# Jukebox.net
KiCad netlist of a schematic drawn in EAGLE
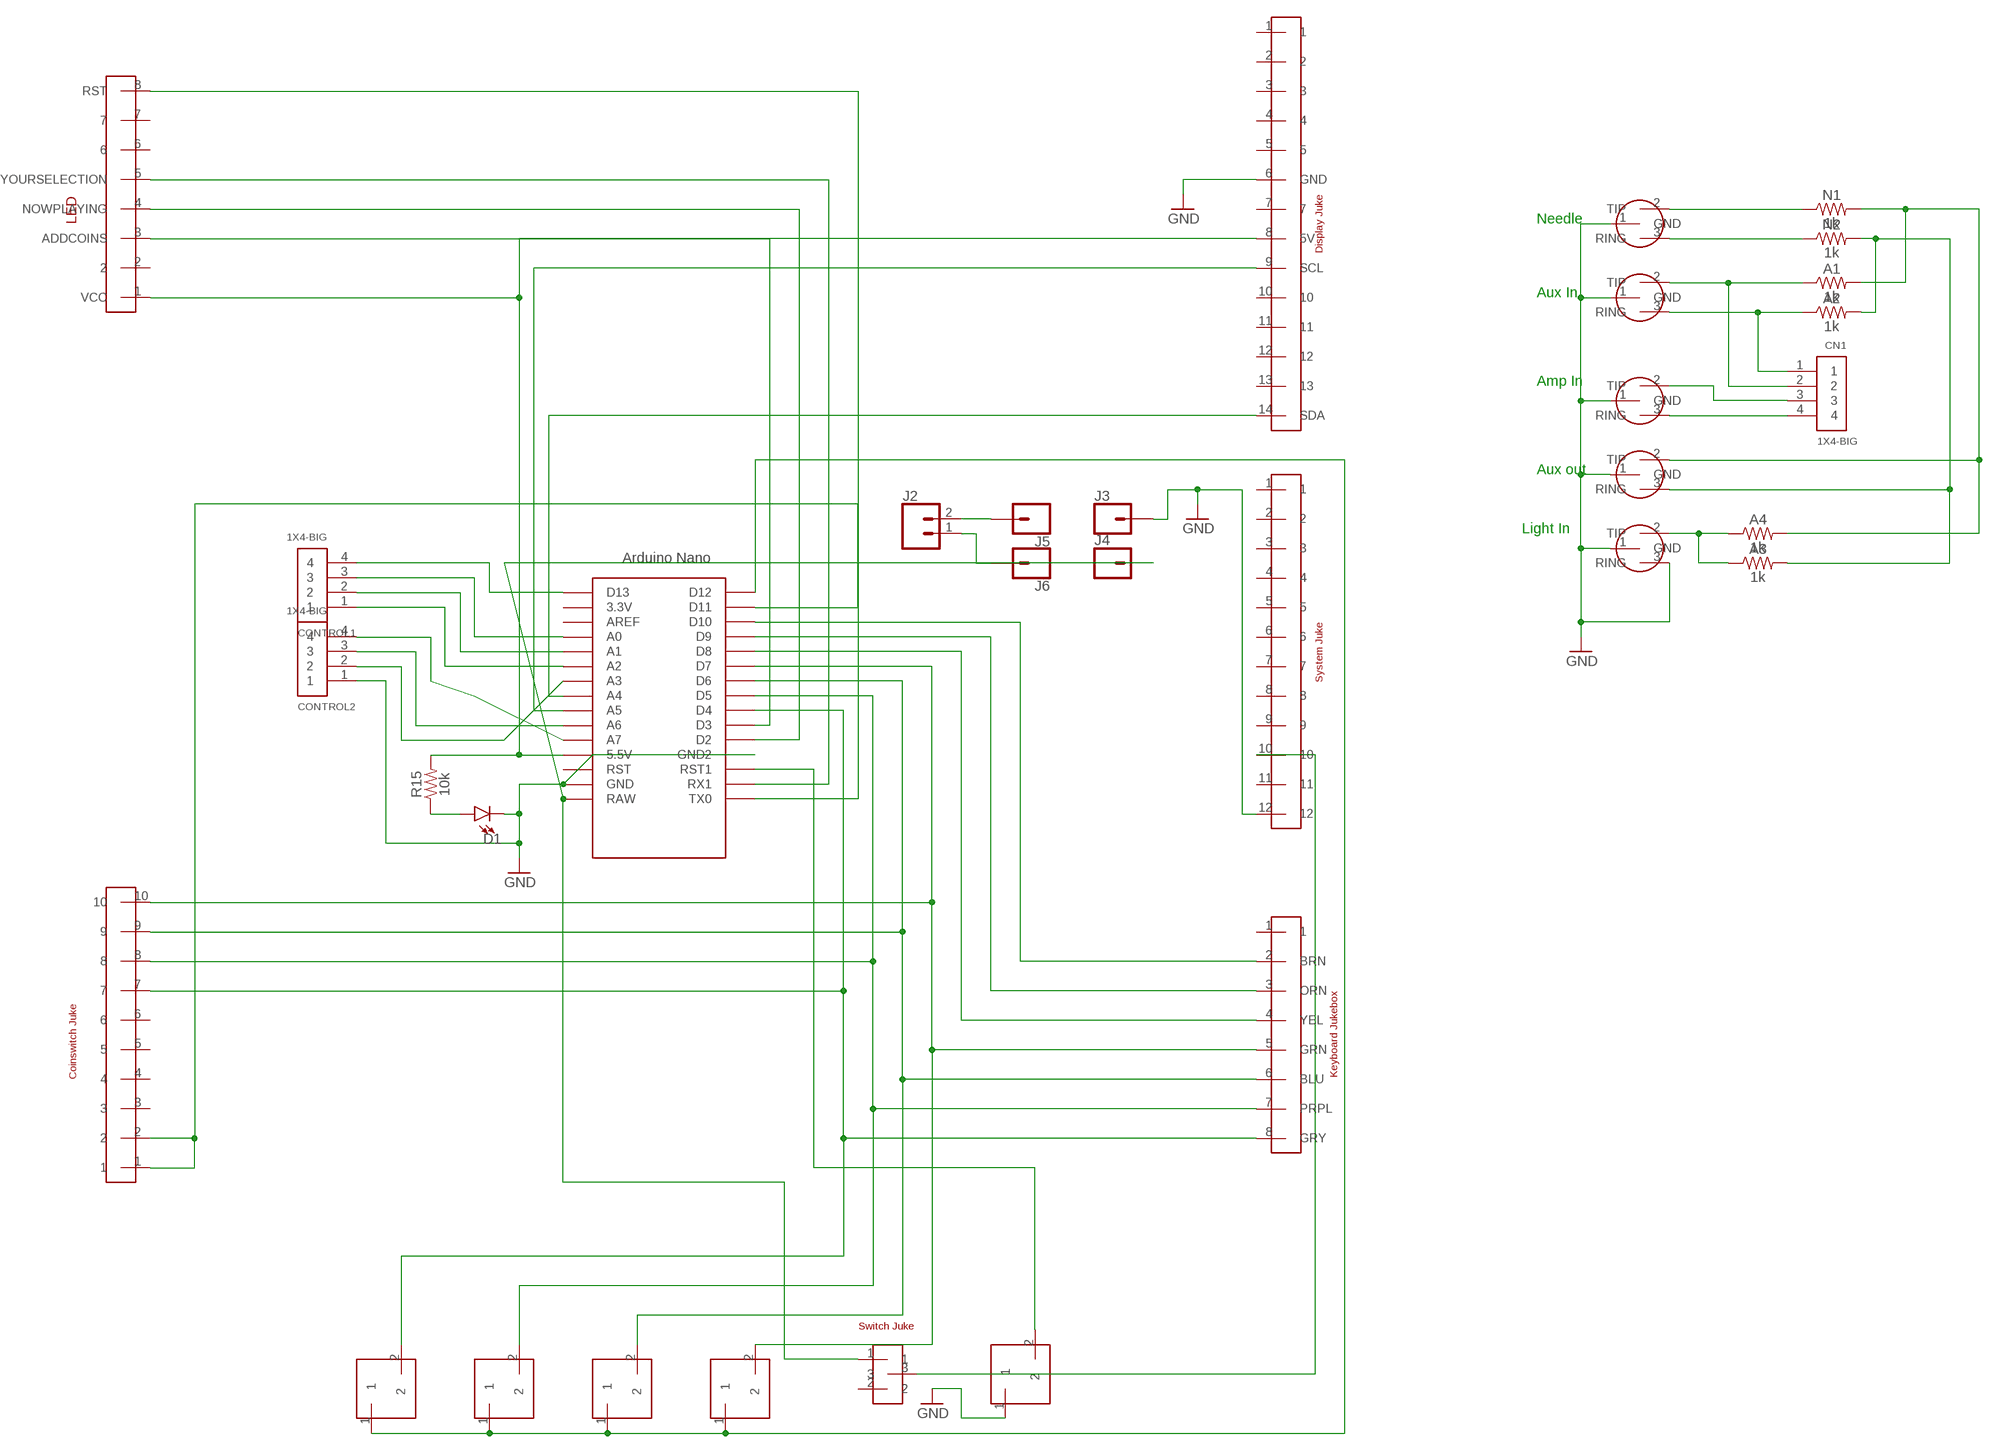
[diagram p0: schematic, sheet 1]

(export (version "E")
  (design (tool "Eeschema 10.0.6"))
  (components
    (comp (ref "A1")
      (value "1k")
      (footprint "eagle-import:AXIAL-0.3")
      (libsource (lib "eagle-import") (part "10KOHM-HORIZ-1/4W-1%"))
    )
    (comp (ref "A2")
      (value "1k")
      (footprint "eagle-import:AXIAL-0.3")
      (libsource (lib "eagle-import") (part "10KOHM-HORIZ-1/4W-1%"))
    )
    (comp (ref "A3")
      (value "1k")
      (footprint "eagle-import:AXIAL-0.3")
      (libsource (lib "eagle-import") (part "10KOHM-HORIZ-1/4W-1%"))
    )
    (comp (ref "A4")
      (value "1k")
      (footprint "eagle-import:AXIAL-0.3")
      (libsource (lib "eagle-import") (part "10KOHM-HORIZ-1/4W-1%"))
    )
    (comp (ref "AUXIN")
      (value "JUKEHEADPHONE")
      (footprint "eagle-import:JUKEHEADPHONE")
      (libsource (lib "eagle-import") (part "JUKEHEADPHONE"))
    )
    (comp (ref "AUXOUT")
      (value "JUKEHEADPHONE")
      (footprint "eagle-import:JUKEHEADPHONE")
      (libsource (lib "eagle-import") (part "JUKEHEADPHONE"))
    )
    (comp (ref "CN1")
      (value "1X4-BIG")
      (footprint "eagle-import:1X04-BIG")
      (libsource (lib "eagle-import") (part "1X4-BIG"))
    )
    (comp (ref "CONTROL1")
      (value "1X4-BIG")
      (footprint "eagle-import:1X04-BIG")
      (libsource (lib "eagle-import") (part "1X4-BIG"))
    )
    (comp (ref "CONTROL2")
      (value "1X4-BIG")
      (footprint "eagle-import:1X04-BIG")
      (libsource (lib "eagle-import") (part "1X4-BIG"))
    )
    (comp (ref "D1")
      (value "LED5MM")
      (footprint "eagle-import:LED_5MM")
      (libsource (lib "eagle-import") (part "LED5MM"))
    )
    (comp (ref "FROMNEEDLE")
      (value "JUKEHEADPHONE")
      (footprint "eagle-import:JUKEHEADPHONE")
      (libsource (lib "eagle-import") (part "JUKEHEADPHONE"))
    )
    (comp (ref "J2")
      (value "CONN_02")
      (footprint "eagle-import:1X02")
      (libsource (lib "eagle-import") (part "CONN_02"))
    )
    (comp (ref "J3")
      (value "CONN_01")
      (footprint "eagle-import:1X01")
      (libsource (lib "eagle-import") (part "CONN_01"))
    )
    (comp (ref "J4")
      (value "CONN_01")
      (footprint "eagle-import:1X01")
      (libsource (lib "eagle-import") (part "CONN_01"))
    )
    (comp (ref "J5")
      (value "CONN_01")
      (footprint "eagle-import:1X01")
      (libsource (lib "eagle-import") (part "CONN_01"))
    )
    (comp (ref "J6")
      (value "CONN_01")
      (footprint "eagle-import:1X01")
      (libsource (lib "eagle-import") (part "CONN_01"))
    )
    (comp (ref "N1")
      (value "1k")
      (footprint "eagle-import:AXIAL-0.3")
      (libsource (lib "eagle-import") (part "10KOHM-HORIZ-1/4W-1%"))
    )
    (comp (ref "N2")
      (value "1k")
      (footprint "eagle-import:AXIAL-0.3")
      (libsource (lib "eagle-import") (part "10KOHM-HORIZ-1/4W-1%"))
    )
    (comp (ref "R15")
      (value "10k")
      (footprint "eagle-import:AXIAL-0.3")
      (libsource (lib "eagle-import") (part "10KOHM-HORIZ-1/4W-1%"))
    )
    (comp (ref "TOAMP")
      (value "JUKEHEADPHONE")
      (footprint "eagle-import:JUKEHEADPHONE")
      (libsource (lib "eagle-import") (part "JUKEHEADPHONE"))
    )
    (comp (ref "TOLIGHT")
      (value "JUKEHEADPHONE")
      (footprint "eagle-import:JUKEHEADPHONE")
      (libsource (lib "eagle-import") (part "JUKEHEADPHONE"))
    )
    (comp (ref "U$1")
      (value "NANO")
      (footprint "eagle-import:NANO")
      (libsource (lib "eagle-import") (part "NANO"))
    )
    (comp (ref "U$5")
      (value "10PINJUKE")
      (footprint "eagle-import:10PINJUKE")
      (libsource (lib "eagle-import") (part "10PINJUKE"))
    )
    (comp (ref "U$6")
      (value "8PINJUKE")
      (footprint "eagle-import:8PINJUKE")
      (libsource (lib "eagle-import") (part "8PINJUKE"))
    )
    (comp (ref "U$7")
      (value "14PINJUKE")
      (footprint "eagle-import:14PINJUKE")
      (libsource (lib "eagle-import") (part "14PINJUKE"))
    )
    (comp (ref "U$8")
      (value "12PINJUKE")
      (footprint "eagle-import:12PINJUKE")
      (libsource (lib "eagle-import") (part "12PINJUKE"))
    )
    (comp (ref "U$9")
      (value "JUKEBUTTON")
      (footprint "eagle-import:JUKEBUTTON")
      (libsource (lib "eagle-import") (part "JUKEBUTTON"))
    )
    (comp (ref "U$10")
      (value "JUKEBUTTON")
      (footprint "eagle-import:JUKEBUTTON")
      (libsource (lib "eagle-import") (part "JUKEBUTTON"))
    )
    (comp (ref "U$11")
      (value "JUKEBUTTON")
      (footprint "eagle-import:JUKEBUTTON")
      (libsource (lib "eagle-import") (part "JUKEBUTTON"))
    )
    (comp (ref "U$12")
      (value "JUKEBUTTON")
      (footprint "eagle-import:JUKEBUTTON")
      (libsource (lib "eagle-import") (part "JUKEBUTTON"))
    )
    (comp (ref "U$13")
      (value "JUKEBUTTON")
      (footprint "eagle-import:JUKEBUTTON")
      (libsource (lib "eagle-import") (part "JUKEBUTTON"))
    )
    (comp (ref "U$14")
      (value "JUKESWITCH")
      (footprint "eagle-import:JUKESWITCH")
      (libsource (lib "eagle-import") (part "JUKESWITCH"))
    )
    (comp (ref "U$17")
      (value "8PINJUKE2")
      (footprint "eagle-import:8PINJUKE")
      (libsource (lib "eagle-import") (part "8PINJUKE2"))
    )
  )
  (nets
    (net (code "1") (name "GND") (class "Default")
      (node (ref "AUXIN") (pin "1") (pinfunction "GND_1") (pintype "bidirectional"))
      (node (ref "AUXOUT") (pin "1") (pinfunction "GND_1") (pintype "bidirectional"))
      (node (ref "CONTROL2") (pin "1") (pinfunction "1_1") (pintype "bidirectional"))
      (node (ref "D1") (pin "K") (pinfunction "C_K") (pintype "passive"))
      (node (ref "FROMNEEDLE") (pin "1") (pinfunction "GND_1") (pintype "bidirectional"))
      (node (ref "J3") (pin "1") (pinfunction "1_1") (pintype "passive"))
      (node (ref "TOAMP") (pin "1") (pinfunction "GND_1") (pintype "bidirectional"))
      (node (ref "TOLIGHT") (pin "1") (pinfunction "GND_1") (pintype "bidirectional"))
      (node (ref "TOLIGHT") (pin "3") (pinfunction "RING_3") (pintype "bidirectional"))
      (node (ref "U$1") (pin "GND") (pinfunction "GND_GND") (pintype "bidirectional"))
      (node (ref "U$1") (pin "GND1") (pinfunction "GND2_GND1") (pintype "bidirectional"))
      (node (ref "U$13") (pin "1") (pinfunction "1_1") (pintype "bidirectional"))
      (node (ref "U$7") (pin "6") (pinfunction "GND_6") (pintype "bidirectional"))
      (node (ref "U$8") (pin "12") (pinfunction "12_12") (pintype "bidirectional"))
    )
    (net (code "2") (name "Net-(A1-1)") (class "Default")
      (node (ref "A1") (pin "P$1") (pinfunction "1_P$1") (pintype "passive"))
      (node (ref "AUXIN") (pin "2") (pinfunction "TIP_2") (pintype "bidirectional"))
      (node (ref "CN1") (pin "2") (pinfunction "2_2") (pintype "bidirectional"))
    )
    (net (code "3") (name "Net-(A1-2)") (class "Default")
      (node (ref "A1") (pin "P$2") (pinfunction "2_P$2") (pintype "passive"))
      (node (ref "A4") (pin "P$2") (pinfunction "2_P$2") (pintype "passive"))
      (node (ref "AUXOUT") (pin "2") (pinfunction "TIP_2") (pintype "bidirectional"))
      (node (ref "N1") (pin "P$2") (pinfunction "2_P$2") (pintype "passive"))
    )
    (net (code "4") (name "Net-(A2-1)") (class "Default")
      (node (ref "A2") (pin "P$1") (pinfunction "1_P$1") (pintype "passive"))
      (node (ref "AUXIN") (pin "3") (pinfunction "RING_3") (pintype "bidirectional"))
      (node (ref "CN1") (pin "1") (pinfunction "1_1") (pintype "bidirectional"))
    )
    (net (code "5") (name "Net-(A2-2)") (class "Default")
      (node (ref "A2") (pin "P$2") (pinfunction "2_P$2") (pintype "passive"))
      (node (ref "A3") (pin "P$2") (pinfunction "2_P$2") (pintype "passive"))
      (node (ref "AUXOUT") (pin "3") (pinfunction "RING_3") (pintype "bidirectional"))
      (node (ref "N2") (pin "P$2") (pinfunction "2_P$2") (pintype "passive"))
    )
    (net (code "6") (name "Net-(A3-1)") (class "Default")
      (node (ref "A3") (pin "P$1") (pinfunction "1_P$1") (pintype "passive"))
      (node (ref "A4") (pin "P$1") (pinfunction "1_P$1") (pintype "passive"))
      (node (ref "TOLIGHT") (pin "2") (pinfunction "TIP_2") (pintype "bidirectional"))
    )
    (net (code "7") (name "Net-(CONTROL1-Pad1)") (class "Default")
      (node (ref "CONTROL1") (pin "1") (pinfunction "1_1") (pintype "bidirectional"))
      (node (ref "U$1") (pin "A2") (pinfunction "A2_A2") (pintype "bidirectional"))
    )
    (net (code "8") (name "Net-(CONTROL1-Pad2)") (class "Default")
      (node (ref "CONTROL1") (pin "2") (pinfunction "2_2") (pintype "bidirectional"))
      (node (ref "U$1") (pin "A1") (pinfunction "A1_A1") (pintype "bidirectional"))
    )
    (net (code "9") (name "Net-(CONTROL1-Pad3)") (class "Default")
      (node (ref "CONTROL1") (pin "3") (pinfunction "3_3") (pintype "bidirectional"))
      (node (ref "U$1") (pin "A0") (pinfunction "A0_A0") (pintype "bidirectional"))
    )
    (net (code "10") (name "Net-(CONTROL1-Pad4)") (class "Default")
      (node (ref "CONTROL1") (pin "4") (pinfunction "4_4") (pintype "bidirectional"))
      (node (ref "U$1") (pin "D13") (pinfunction "D13_D13") (pintype "bidirectional"))
    )
    (net (code "11") (name "Net-(CONTROL2-Pad2)") (class "Default")
      (node (ref "CONTROL2") (pin "2") (pinfunction "2_2") (pintype "bidirectional"))
      (node (ref "U$1") (pin "A3") (pinfunction "A3_A3") (pintype "bidirectional"))
    )
    (net (code "12") (name "Net-(CONTROL2-Pad3)") (class "Default")
      (node (ref "CONTROL2") (pin "3") (pinfunction "3_3") (pintype "bidirectional"))
      (node (ref "U$1") (pin "A6") (pinfunction "A6_A6") (pintype "bidirectional"))
    )
    (net (code "13") (name "Net-(CONTROL2-Pad4)") (class "Default")
      (node (ref "CONTROL2") (pin "4") (pinfunction "4_4") (pintype "bidirectional"))
      (node (ref "U$1") (pin "A7") (pinfunction "A7_A7") (pintype "bidirectional"))
    )
    (net (code "14") (name "Net-(FROMNEEDLE-RING)") (class "Default")
      (node (ref "FROMNEEDLE") (pin "3") (pinfunction "RING_3") (pintype "bidirectional"))
      (node (ref "N2") (pin "P$1") (pinfunction "1_P$1") (pintype "passive"))
    )
    (net (code "15") (name "Net-(FROMNEEDLE-TIP)") (class "Default")
      (node (ref "FROMNEEDLE") (pin "2") (pinfunction "TIP_2") (pintype "bidirectional"))
      (node (ref "N1") (pin "P$1") (pinfunction "1_P$1") (pintype "passive"))
    )
    (net (code "16") (name "Net-(J2-Pad1)") (class "Default")
      (node (ref "J2") (pin "1") (pinfunction "1_1") (pintype "passive"))
      (node (ref "J6") (pin "1") (pinfunction "1_1") (pintype "passive"))
    )
    (net (code "17") (name "Net-(J2-Pad2)") (class "Default")
      (node (ref "J2") (pin "2") (pinfunction "2_2") (pintype "passive"))
      (node (ref "J5") (pin "1") (pinfunction "1_1") (pintype "passive"))
    )
    (net (code "18") (name "Net-(J4-Pad1)") (class "Default")
      (node (ref "J4") (pin "1") (pinfunction "1_1") (pintype "passive"))
      (node (ref "U$1") (pin "RAW") (pinfunction "RAW_RAW") (pintype "bidirectional"))
      (node (ref "U$14") (pin "1") (pinfunction "1_1") (pintype "bidirectional"))
    )
    (net (code "19") (name "Net-(R15-1)") (class "Default")
      (node (ref "D1") (pin "A") (pinfunction "A_A") (pintype "passive"))
      (node (ref "R15") (pin "P$1") (pinfunction "1_P$1") (pintype "passive"))
    )
    (net (code "20") (name "Net-(R15-2)") (class "Default")
      (node (ref "R15") (pin "P$2") (pinfunction "2_P$2") (pintype "passive"))
      (node (ref "U$1") (pin "5V") (pinfunction "5.5V_5V") (pintype "bidirectional"))
      (node (ref "U$17") (pin "1") (pinfunction "VCC_1") (pintype "bidirectional"))
      (node (ref "U$7") (pin "8") (pinfunction "5V_8") (pintype "bidirectional"))
    )
    (net (code "21") (name "Net-(TOAMP-RING)") (class "Default")
      (node (ref "CN1") (pin "4") (pinfunction "4_4") (pintype "bidirectional"))
      (node (ref "TOAMP") (pin "3") (pinfunction "RING_3") (pintype "bidirectional"))
    )
    (net (code "22") (name "Net-(TOAMP-TIP)") (class "Default")
      (node (ref "CN1") (pin "3") (pinfunction "3_3") (pintype "bidirectional"))
      (node (ref "TOAMP") (pin "2") (pinfunction "TIP_2") (pintype "bidirectional"))
    )
    (net (code "23") (name "Net-(U$1-PadD11)") (class "Default")
      (node (ref "U$1") (pin "D11") (pinfunction "D11_D11") (pintype "bidirectional"))
      (node (ref "U$5") (pin "1") (pinfunction "1_1") (pintype "bidirectional"))
      (node (ref "U$5") (pin "2") (pinfunction "2_2") (pintype "bidirectional"))
    )
    (net (code "24") (name "Net-(U$1-PadD12)") (class "Default")
      (node (ref "U$1") (pin "D12") (pinfunction "D12_D12") (pintype "bidirectional"))
      (node (ref "U$10") (pin "1") (pinfunction "1_1") (pintype "bidirectional"))
      (node (ref "U$11") (pin "1") (pinfunction "1_1") (pintype "bidirectional"))
      (node (ref "U$12") (pin "1") (pinfunction "1_1") (pintype "bidirectional"))
      (node (ref "U$9") (pin "1") (pinfunction "1_1") (pintype "bidirectional"))
    )
    (net (code "25") (name "Net-(U$1-PadRST1)") (class "Default")
      (node (ref "U$1") (pin "RST1") (pinfunction "RST1_RST1") (pintype "bidirectional"))
      (node (ref "U$13") (pin "2") (pinfunction "2_2") (pintype "bidirectional"))
    )
    (net (code "26") (name "Net-(U$6-BLU)") (class "Default")
      (node (ref "U$1") (pin "D6") (pinfunction "D6_D6") (pintype "bidirectional"))
      (node (ref "U$11") (pin "2") (pinfunction "2_2") (pintype "bidirectional"))
      (node (ref "U$5") (pin "9") (pinfunction "9_9") (pintype "bidirectional"))
      (node (ref "U$6") (pin "6") (pinfunction "BLU_6") (pintype "bidirectional"))
    )
    (net (code "27") (name "Net-(U$6-BRN)") (class "Default")
      (node (ref "U$1") (pin "D10") (pinfunction "D10_D10") (pintype "bidirectional"))
      (node (ref "U$6") (pin "2") (pinfunction "BRN_2") (pintype "bidirectional"))
    )
    (net (code "28") (name "Net-(U$6-GRN)") (class "Default")
      (node (ref "U$1") (pin "D7") (pinfunction "D7_D7") (pintype "bidirectional"))
      (node (ref "U$12") (pin "2") (pinfunction "2_2") (pintype "bidirectional"))
      (node (ref "U$5") (pin "10") (pinfunction "10_10") (pintype "bidirectional"))
      (node (ref "U$6") (pin "5") (pinfunction "GRN_5") (pintype "bidirectional"))
    )
    (net (code "29") (name "Net-(U$6-GRY)") (class "Default")
      (node (ref "U$1") (pin "D4") (pinfunction "D4_D4") (pintype "bidirectional"))
      (node (ref "U$5") (pin "7") (pinfunction "7_7") (pintype "bidirectional"))
      (node (ref "U$6") (pin "8") (pinfunction "GRY_8") (pintype "bidirectional"))
      (node (ref "U$9") (pin "2") (pinfunction "2_2") (pintype "bidirectional"))
    )
    (net (code "30") (name "Net-(U$6-ORN)") (class "Default")
      (node (ref "U$1") (pin "D9") (pinfunction "D9_D9") (pintype "bidirectional"))
      (node (ref "U$6") (pin "3") (pinfunction "ORN_3") (pintype "bidirectional"))
    )
    (net (code "31") (name "Net-(U$6-PRPL)") (class "Default")
      (node (ref "U$1") (pin "D5") (pinfunction "D5_D5") (pintype "bidirectional"))
      (node (ref "U$10") (pin "2") (pinfunction "2_2") (pintype "bidirectional"))
      (node (ref "U$5") (pin "8") (pinfunction "8_8") (pintype "bidirectional"))
      (node (ref "U$6") (pin "7") (pinfunction "PRPL_7") (pintype "bidirectional"))
    )
    (net (code "32") (name "Net-(U$6-YEL)") (class "Default")
      (node (ref "U$1") (pin "D8") (pinfunction "D8_D8") (pintype "bidirectional"))
      (node (ref "U$6") (pin "4") (pinfunction "YEL_4") (pintype "bidirectional"))
    )
    (net (code "33") (name "Net-(U$7-SCL)") (class "Default")
      (node (ref "U$1") (pin "A5") (pinfunction "A5_A5") (pintype "bidirectional"))
      (node (ref "U$7") (pin "9") (pinfunction "SCL_9") (pintype "bidirectional"))
    )
    (net (code "34") (name "Net-(U$7-SDA)") (class "Default")
      (node (ref "U$1") (pin "A4") (pinfunction "A4_A4") (pintype "bidirectional"))
      (node (ref "U$7") (pin "14") (pinfunction "SDA_14") (pintype "bidirectional"))
    )
    (net (code "35") (name "Net-(U$14-Pad3)") (class "Default")
      (node (ref "U$14") (pin "3") (pinfunction "3_3") (pintype "bidirectional"))
      (node (ref "U$8") (pin "10") (pinfunction "10_10") (pintype "bidirectional"))
    )
    (net (code "36") (name "Net-(U$17-ADDCOINS)") (class "Default")
      (node (ref "U$1") (pin "D3") (pinfunction "D3_D3") (pintype "bidirectional"))
      (node (ref "U$17") (pin "3") (pinfunction "ADDCOINS_3") (pintype "bidirectional"))
    )
    (net (code "37") (name "Net-(U$17-NOWPLAYING)") (class "Default")
      (node (ref "U$1") (pin "D2") (pinfunction "D2_D2") (pintype "bidirectional"))
      (node (ref "U$17") (pin "4") (pinfunction "NOWPLAYING_4") (pintype "bidirectional"))
    )
    (net (code "38") (name "Net-(U$17-RST)") (class "Default")
      (node (ref "U$1") (pin "TX0") (pinfunction "TX0_TX0") (pintype "bidirectional"))
      (node (ref "U$17") (pin "8") (pinfunction "RST_8") (pintype "bidirectional"))
    )
    (net (code "39") (name "Net-(U$17-YOURSELECTION)") (class "Default")
      (node (ref "U$1") (pin "RX1") (pinfunction "RX1_RX1") (pintype "bidirectional"))
      (node (ref "U$17") (pin "5") (pinfunction "YOURSELECTION_5") (pintype "bidirectional"))
    )
    (net (code "40") (name "unconnected-(U$1-Pad3.3V)") (class "Default")
      (node (ref "U$1") (pin "3.3V") (pinfunction "3.3V_3.3V") (pintype "bidirectional"))
    )
    (net (code "41") (name "unconnected-(U$1-PadAREF)") (class "Default")
      (node (ref "U$1") (pin "AREF") (pinfunction "AREF_AREF") (pintype "bidirectional"))
    )
    (net (code "42") (name "unconnected-(U$1-PadRST)") (class "Default")
      (node (ref "U$1") (pin "RST") (pinfunction "RST_RST") (pintype "bidirectional"))
    )
    (net (code "43") (name "unconnected-(U$5-Pad3)") (class "Default")
      (node (ref "U$5") (pin "3") (pinfunction "3_3") (pintype "bidirectional"))
    )
    (net (code "44") (name "unconnected-(U$5-Pad4)") (class "Default")
      (node (ref "U$5") (pin "4") (pinfunction "4_4") (pintype "bidirectional"))
    )
    (net (code "45") (name "unconnected-(U$5-Pad5)") (class "Default")
      (node (ref "U$5") (pin "5") (pinfunction "5_5") (pintype "bidirectional"))
    )
    (net (code "46") (name "unconnected-(U$5-Pad6)") (class "Default")
      (node (ref "U$5") (pin "6") (pinfunction "6_6") (pintype "bidirectional"))
    )
    (net (code "47") (name "unconnected-(U$6-Pad1)") (class "Default")
      (node (ref "U$6") (pin "1") (pinfunction "1_1") (pintype "bidirectional"))
    )
    (net (code "48") (name "unconnected-(U$7-Pad1)") (class "Default")
      (node (ref "U$7") (pin "1") (pinfunction "1_1") (pintype "bidirectional"))
    )
    (net (code "49") (name "unconnected-(U$7-Pad2)") (class "Default")
      (node (ref "U$7") (pin "2") (pinfunction "2_2") (pintype "bidirectional"))
    )
    (net (code "50") (name "unconnected-(U$7-Pad3)") (class "Default")
      (node (ref "U$7") (pin "3") (pinfunction "3_3") (pintype "bidirectional"))
    )
    (net (code "51") (name "unconnected-(U$7-Pad4)") (class "Default")
      (node (ref "U$7") (pin "4") (pinfunction "4_4") (pintype "bidirectional"))
    )
    (net (code "52") (name "unconnected-(U$7-Pad5)") (class "Default")
      (node (ref "U$7") (pin "5") (pinfunction "5_5") (pintype "bidirectional"))
    )
    (net (code "53") (name "unconnected-(U$7-Pad7)") (class "Default")
      (node (ref "U$7") (pin "7") (pinfunction "7_7") (pintype "bidirectional"))
    )
    (net (code "54") (name "unconnected-(U$7-Pad10)") (class "Default")
      (node (ref "U$7") (pin "10") (pinfunction "10_10") (pintype "bidirectional"))
    )
    (net (code "55") (name "unconnected-(U$7-Pad11)") (class "Default")
      (node (ref "U$7") (pin "11") (pinfunction "11_11") (pintype "bidirectional"))
    )
    (net (code "56") (name "unconnected-(U$7-Pad12)") (class "Default")
      (node (ref "U$7") (pin "12") (pinfunction "12_12") (pintype "bidirectional"))
    )
    (net (code "57") (name "unconnected-(U$7-Pad13)") (class "Default")
      (node (ref "U$7") (pin "13") (pinfunction "13_13") (pintype "bidirectional"))
    )
    (net (code "58") (name "unconnected-(U$8-Pad1)") (class "Default")
      (node (ref "U$8") (pin "1") (pinfunction "1_1") (pintype "bidirectional"))
    )
    (net (code "59") (name "unconnected-(U$8-Pad2)") (class "Default")
      (node (ref "U$8") (pin "2") (pinfunction "2_2") (pintype "bidirectional"))
    )
    (net (code "60") (name "unconnected-(U$8-Pad3)") (class "Default")
      (node (ref "U$8") (pin "3") (pinfunction "3_3") (pintype "bidirectional"))
    )
    (net (code "61") (name "unconnected-(U$8-Pad4)") (class "Default")
      (node (ref "U$8") (pin "4") (pinfunction "4_4") (pintype "bidirectional"))
    )
    (net (code "62") (name "unconnected-(U$8-Pad5)") (class "Default")
      (node (ref "U$8") (pin "5") (pinfunction "5_5") (pintype "bidirectional"))
    )
    (net (code "63") (name "unconnected-(U$8-Pad6)") (class "Default")
      (node (ref "U$8") (pin "6") (pinfunction "6_6") (pintype "bidirectional"))
    )
    (net (code "64") (name "unconnected-(U$8-Pad7)") (class "Default")
      (node (ref "U$8") (pin "7") (pinfunction "7_7") (pintype "bidirectional"))
    )
    (net (code "65") (name "unconnected-(U$8-Pad8)") (class "Default")
      (node (ref "U$8") (pin "8") (pinfunction "8_8") (pintype "bidirectional"))
    )
    (net (code "66") (name "unconnected-(U$8-Pad9)") (class "Default")
      (node (ref "U$8") (pin "9") (pinfunction "9_9") (pintype "bidirectional"))
    )
    (net (code "67") (name "unconnected-(U$8-Pad11)") (class "Default")
      (node (ref "U$8") (pin "11") (pinfunction "11_11") (pintype "bidirectional"))
    )
    (net (code "68") (name "unconnected-(U$14-Pad2)") (class "Default")
      (node (ref "U$14") (pin "2") (pinfunction "2_2") (pintype "bidirectional"))
    )
    (net (code "69") (name "unconnected-(U$17-Pad2)") (class "Default")
      (node (ref "U$17") (pin "2") (pinfunction "2_2") (pintype "bidirectional"))
    )
    (net (code "70") (name "unconnected-(U$17-Pad6)") (class "Default")
      (node (ref "U$17") (pin "6") (pinfunction "6_6") (pintype "bidirectional"))
    )
    (net (code "71") (name "unconnected-(U$17-Pad7)") (class "Default")
      (node (ref "U$17") (pin "7") (pinfunction "7_7") (pintype "bidirectional"))
    )
  )
)
